# FPGA.net
KiCad netlist of a schematic drawn in Altium Designer
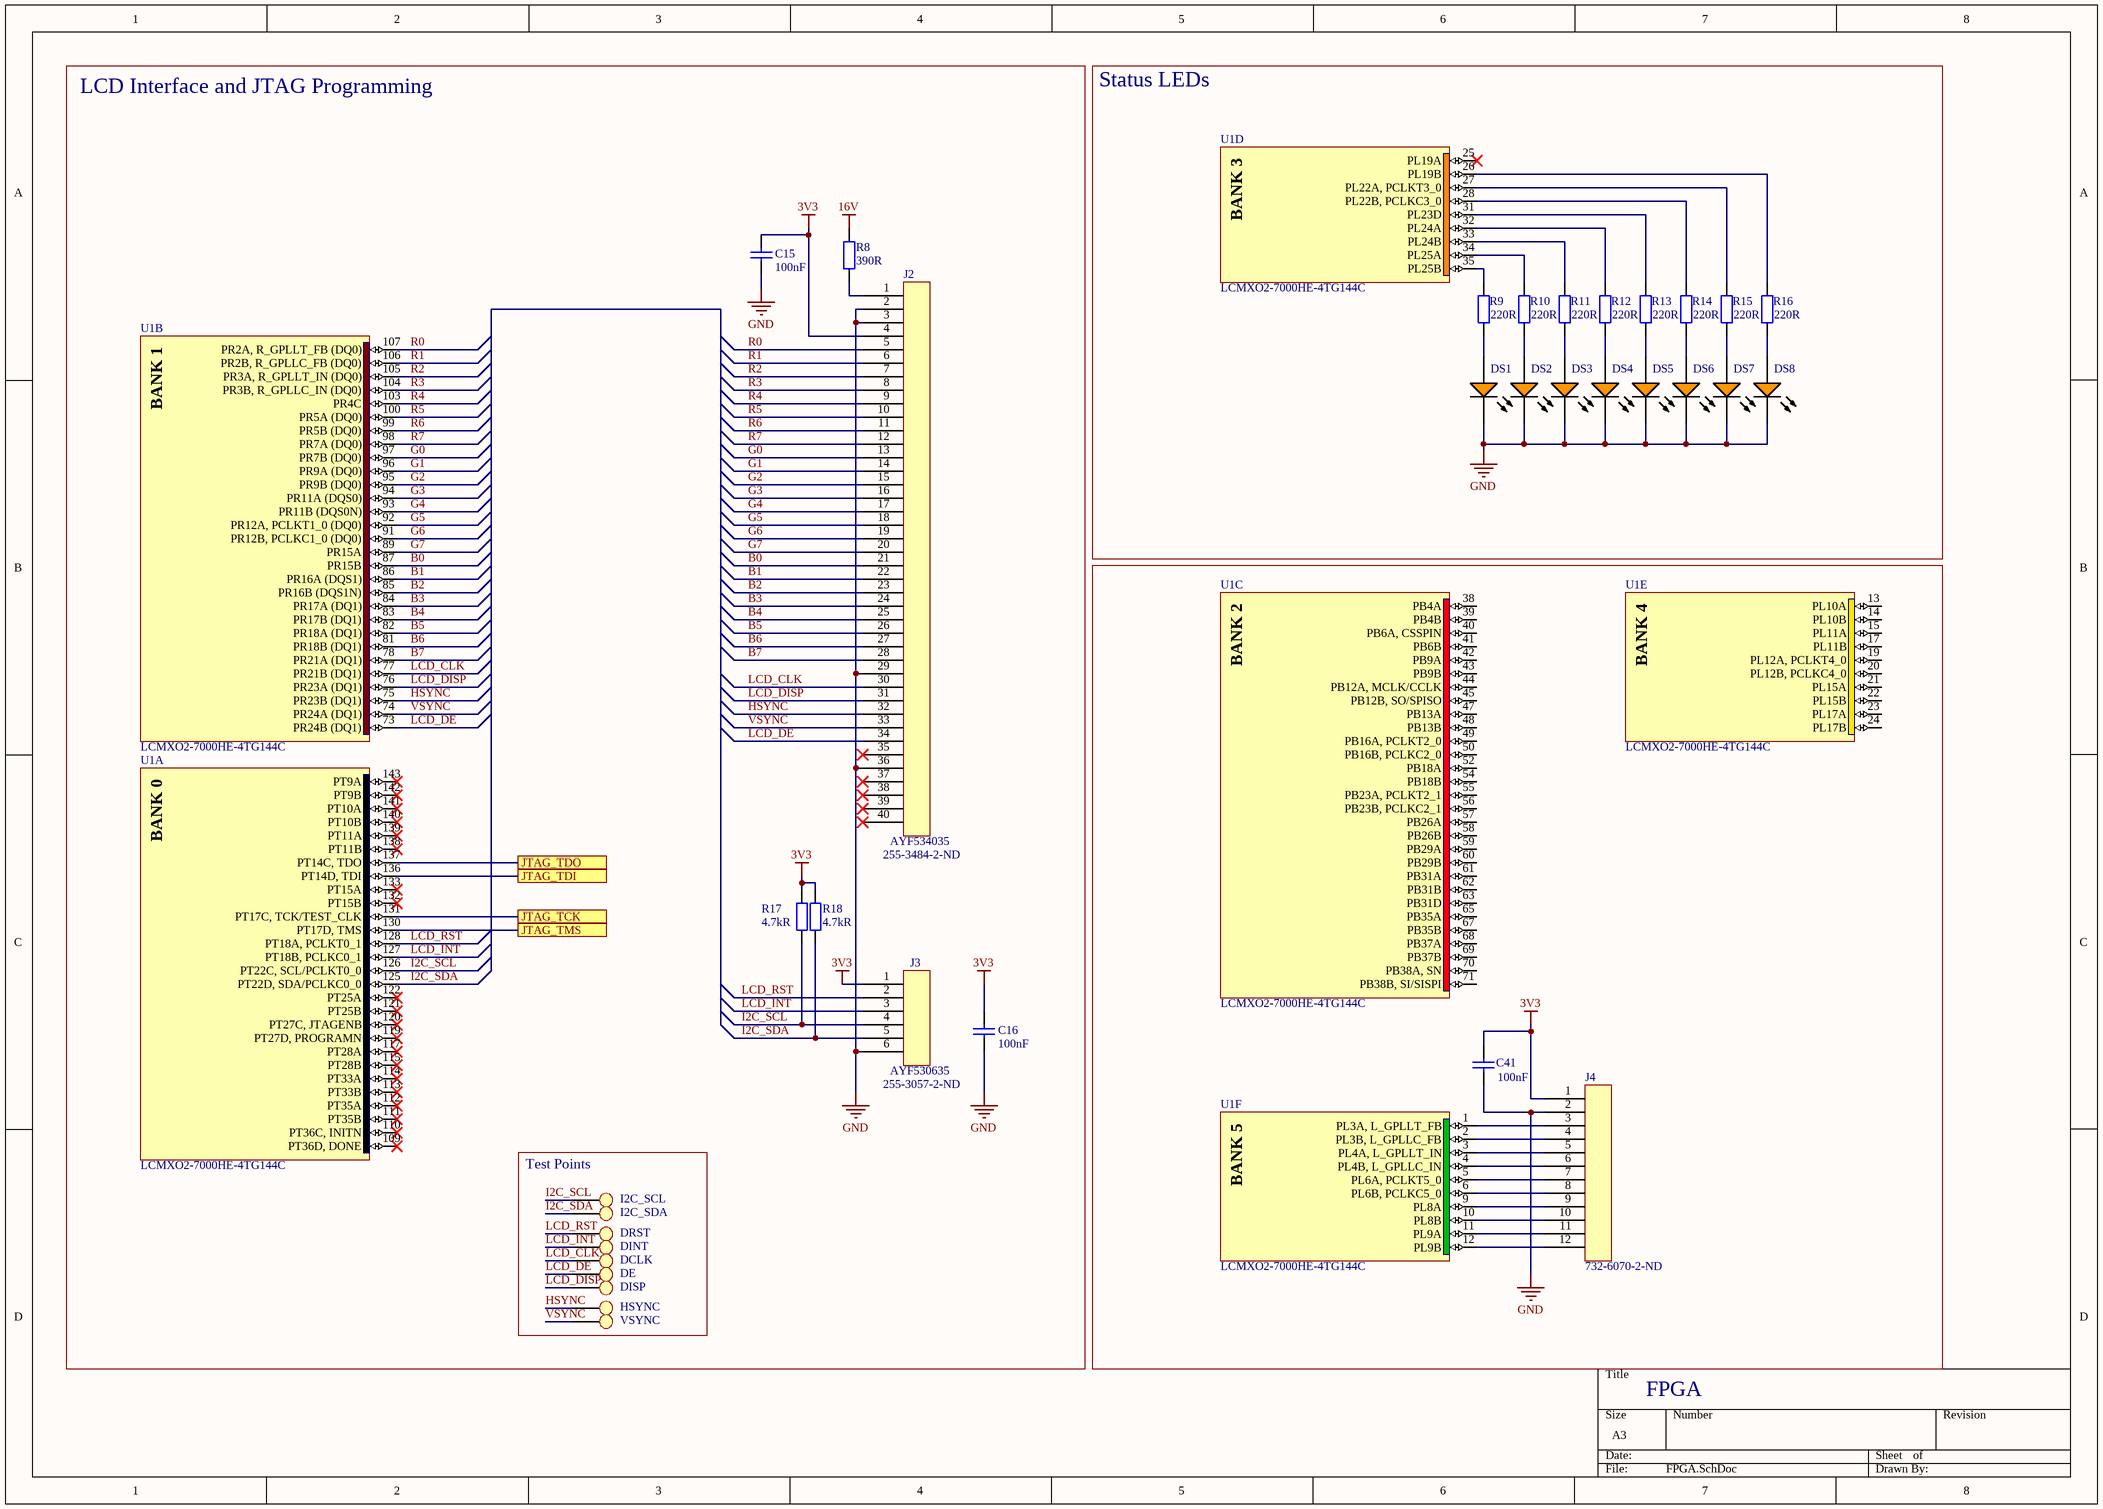
[diagram p0: FPGA.SchDoc]

(export (version "E")
  (design (tool "Eeschema 10.0.6"))
  (components
    (comp (ref "C15")
      (value "C0402C104K4RACTU")
      (footprint "CAP_0402_imperial")
      (description "CAP CER 0.1UF 16V X7R 0402")
      (fields
        (field (name "MANUFACTURER") "KEMET")
        (field (name "MANUFACTURER PART NUMBER") "C0402C104K4RAC-TU")
        (field (name "CAPACITANCE") "100nF")
      )
      (libsource (lib "LCD-Controller") (part "C0402C104K4RAC-TU"))
    )
    (comp (ref "C16")
      (value "C0402C104K4RACTU")
      (footprint "CAP_0402_imperial")
      (description "CAP CER 0.1UF 16V X7R 0402")
      (fields
        (field (name "MANUFACTURER") "KEMET")
        (field (name "MANUFACTURER PART NUMBER") "C0402C104K4RAC-TU")
        (field (name "CAPACITANCE") "100nF")
      )
      (libsource (lib "LCD-Controller") (part "C0402C104K4RAC-TU"))
    )
    (comp (ref "C41")
      (value "C0402C104K4RAC-TU")
      (footprint "CAP_0402_imperial")
      (description "CAP CER 0.1UF 16V X7R 0402")
      (fields
        (field (name "MANUFACTURER") "KEMET")
        (field (name "TOLERANCE") "10%")
        (field (name "CAPACITANCE") "100nF")
      )
      (libsource (lib "LCD-Controller") (part "C0402C104K4RAC-TU"))
    )
    (comp (ref "DCLK") (value "TP") (footprint "TP_0.75DIA") (libsource (lib "LCD-Controller") (part "TP")))
    (comp (ref "DE") (value "TP") (footprint "TP_0.75DIA") (libsource (lib "LCD-Controller") (part "TP")))
    (comp (ref "DINT") (value "TP") (footprint "TP_0.75DIA") (libsource (lib "LCD-Controller") (part "TP")))
    (comp (ref "DISP") (value "TP") (footprint "TP_0.75DIA") (libsource (lib "LCD-Controller") (part "TP")))
    (comp (ref "DRST") (value "TP") (footprint "TP_0.75DIA") (libsource (lib "LCD-Controller") (part "TP")))
    (comp (ref "DS1")
      (value "APG1608SEKC/T")
      (footprint "KING-LED0603-25-ORANGE_V")
      (description "LED, SMT, 0603(1608), 0.25mm Tthickness, Super Bright Orange")
      (libsource (lib "Altium Content Vault") (part "KING-LED_ORANGE_A1K2-2"))
    )
    (comp (ref "DS2")
      (value "APG1608SEKC/T")
      (footprint "KING-LED0603-25-ORANGE_V")
      (description "LED, SMT, 0603(1608), 0.25mm Tthickness, Super Bright Orange")
      (libsource (lib "Altium Content Vault") (part "KING-LED_ORANGE_A1K2-2"))
    )
    (comp (ref "DS3")
      (value "APG1608SEKC/T")
      (footprint "KING-LED0603-25-ORANGE_V")
      (description "LED, SMT, 0603(1608), 0.25mm Tthickness, Super Bright Orange")
      (libsource (lib "Altium Content Vault") (part "KING-LED_ORANGE_A1K2-2"))
    )
    (comp (ref "DS4")
      (value "APG1608SEKC/T")
      (footprint "KING-LED0603-25-ORANGE_V")
      (description "LED, SMT, 0603(1608), 0.25mm Tthickness, Super Bright Orange")
      (libsource (lib "Altium Content Vault") (part "KING-LED_ORANGE_A1K2-2"))
    )
    (comp (ref "DS5")
      (value "APG1608SEKC/T")
      (footprint "KING-LED0603-25-ORANGE_V")
      (description "LED, SMT, 0603(1608), 0.25mm Tthickness, Super Bright Orange")
      (libsource (lib "Altium Content Vault") (part "KING-LED_ORANGE_A1K2-2"))
    )
    (comp (ref "DS6")
      (value "APG1608SEKC/T")
      (footprint "KING-LED0603-25-ORANGE_V")
      (description "LED, SMT, 0603(1608), 0.25mm Tthickness, Super Bright Orange")
      (libsource (lib "Altium Content Vault") (part "KING-LED_ORANGE_A1K2-2"))
    )
    (comp (ref "DS7")
      (value "APG1608SEKC/T")
      (footprint "KING-LED0603-25-ORANGE_V")
      (description "LED, SMT, 0603(1608), 0.25mm Tthickness, Super Bright Orange")
      (libsource (lib "Altium Content Vault") (part "KING-LED_ORANGE_A1K2-2"))
    )
    (comp (ref "DS8")
      (value "APG1608SEKC/T")
      (footprint "KING-LED0603-25-ORANGE_V")
      (description "LED, SMT, 0603(1608), 0.25mm Tthickness, Super Bright Orange")
      (libsource (lib "Altium Content Vault") (part "KING-LED_ORANGE_A1K2-2"))
    )
    (comp (ref "HSYNC") (value "TP") (footprint "TP_0.75DIA") (libsource (lib "LCD-Controller") (part "TP")))
    (comp (ref "I2C_SCL")
      (value "TP")
      (footprint "TP_0.75DIA")
      (libsource (lib "LCD-Controller") (part "TP"))
    )
    (comp (ref "I2C_SDA")
      (value "TP")
      (footprint "TP_0.75DIA")
      (libsource (lib "LCD-Controller") (part "TP"))
    )
    (comp (ref "J2")
      (value "AYF534035")
      (footprint "AYF534035")
      (description "CONN FFC FPC 40POS 0.50MM R/A")
      (fields
        (field (name "MANUFACTURER") "Panasonic")
        (field (name "SUPPLIER PART NUMBER 1") "255-3484-2-ND")
      )
      (libsource (lib "Connectors") (part "AYF534035"))
    )
    (comp (ref "J3")
      (value "AYF530635")
      (footprint "AYF530635")
      (description "CONN FFC FPC 6POS 0.50MM R/A")
      (fields
        (field (name "MANUFACTURER") "Panasonic")
        (field (name "SUPPLIER PART NUMBER 1") "255-3057-2-ND")
      )
      (libsource (lib "Connectors") (part "AYF530635"))
    )
    (comp (ref "J4")
      (value "610112249121")
      (footprint "610112249121")
      (description "Pin header 12P, 610112249121, Würth Elektronik")
      (fields
        (field (name "MANUFACTURER") "Wurth Electronics")
        (field (name "SUPPLIER PART NUMBER 1") "732-6070-2-ND")
      )
      (libsource (lib "LCD-Controller") (part "610112249121"))
    )
    (comp (ref "R8")
      (value "390R 1% 2512(6432)")
      (footprint "RES_0603_imperial")
      (fields
        (field (name "TOLERANCE") "0.1%")
        (field (name "MANUFACTURER") "Panasonic")
        (field (name "MANUFACTURER PART NUMBER") "ERA3AEB391V")
        (field (name "RESISTANCE") "390R")
      )
      (libsource (lib "LCD-Controller") (part "ERA3AEB391V"))
    )
    (comp (ref "R9")
      (value "220R 1% 0603(1608)")
      (footprint "RES_0603_imperial")
      (description "Res Thin Film 0603 220 Ohm 0.1% 1/10W ±25ppm/C Molded SMD Punched Carrier T/R")
      (fields
        (field (name "TOLERANCE") "0.1%")
        (field (name "MANUFACTURER") "Panasonic")
        (field (name "RESISTANCE") "220R")
      )
      (libsource (lib "LCD-Controller") (part "ERA-3AEB221V"))
    )
    (comp (ref "R10")
      (value "220R 1% 0603(1608)")
      (footprint "RES_0603_imperial")
      (description "Res Thin Film 0603 220 Ohm 0.1% 1/10W ±25ppm/C Molded SMD Punched Carrier T/R")
      (fields
        (field (name "TOLERANCE") "0.1%")
        (field (name "MANUFACTURER") "Panasonic")
        (field (name "RESISTANCE") "220R")
      )
      (libsource (lib "LCD-Controller") (part "ERA-3AEB221V"))
    )
    (comp (ref "R11")
      (value "220R 1% 0603(1608)")
      (footprint "RES_0603_imperial")
      (description "Res Thin Film 0603 220 Ohm 0.1% 1/10W ±25ppm/C Molded SMD Punched Carrier T/R")
      (fields
        (field (name "TOLERANCE") "0.1%")
        (field (name "MANUFACTURER") "Panasonic")
        (field (name "RESISTANCE") "220R")
      )
      (libsource (lib "LCD-Controller") (part "ERA-3AEB221V"))
    )
    (comp (ref "R12")
      (value "220R 1% 0603(1608)")
      (footprint "RES_0603_imperial")
      (description "Res Thin Film 0603 220 Ohm 0.1% 1/10W ±25ppm/C Molded SMD Punched Carrier T/R")
      (fields
        (field (name "TOLERANCE") "0.1%")
        (field (name "MANUFACTURER") "Panasonic")
        (field (name "RESISTANCE") "220R")
      )
      (libsource (lib "LCD-Controller") (part "ERA-3AEB221V"))
    )
    (comp (ref "R13")
      (value "220R 1% 0603(1608)")
      (footprint "RES_0603_imperial")
      (description "Res Thin Film 0603 220 Ohm 0.1% 1/10W ±25ppm/C Molded SMD Punched Carrier T/R")
      (fields
        (field (name "TOLERANCE") "0.1%")
        (field (name "MANUFACTURER") "Panasonic")
        (field (name "RESISTANCE") "220R")
      )
      (libsource (lib "LCD-Controller") (part "ERA-3AEB221V"))
    )
    (comp (ref "R14")
      (value "220R 1% 0603(1608)")
      (footprint "RES_0603_imperial")
      (description "Res Thin Film 0603 220 Ohm 0.1% 1/10W ±25ppm/C Molded SMD Punched Carrier T/R")
      (fields
        (field (name "TOLERANCE") "0.1%")
        (field (name "MANUFACTURER") "Panasonic")
        (field (name "RESISTANCE") "220R")
      )
      (libsource (lib "LCD-Controller") (part "ERA-3AEB221V"))
    )
    (comp (ref "R15")
      (value "220R 1% 0603(1608)")
      (footprint "RES_0603_imperial")
      (description "Res Thin Film 0603 220 Ohm 0.1% 1/10W ±25ppm/C Molded SMD Punched Carrier T/R")
      (fields
        (field (name "TOLERANCE") "0.1%")
        (field (name "MANUFACTURER") "Panasonic")
        (field (name "RESISTANCE") "220R")
      )
      (libsource (lib "LCD-Controller") (part "ERA-3AEB221V"))
    )
    (comp (ref "R16")
      (value "220R 1% 0603(1608)")
      (footprint "RES_0603_imperial")
      (description "Res Thin Film 0603 220 Ohm 0.1% 1/10W ±25ppm/C Molded SMD Punched Carrier T/R")
      (fields
        (field (name "TOLERANCE") "0.1%")
        (field (name "MANUFACTURER") "Panasonic")
        (field (name "RESISTANCE") "220R")
      )
      (libsource (lib "LCD-Controller") (part "ERA-3AEB221V"))
    )
    (comp (ref "R17")
      (value "4K7 1% 0603(1608)")
      (footprint "RES_0603_imperial")
      (description "Res Thin Film 0603 4.7K Ohm 0.1% 0.1W(1/10W) ±25ppm/C Molded SMD Automotive Punched T/R")
      (fields
        (field (name "TOLERANCE") "0.1%")
        (field (name "MANUFACTURER") "Panasonic")
        (field (name "RESISTANCE") "4.7kR")
      )
      (libsource (lib "LCD-Controller") (part "ERA-3AEB472V"))
    )
    (comp (ref "R18")
      (value "4K7 1% 0603(1608)")
      (footprint "RES_0603_imperial")
      (description "Res Thin Film 0603 4.7K Ohm 0.1% 0.1W(1/10W) ±25ppm/C Molded SMD Automotive Punched T/R")
      (fields
        (field (name "TOLERANCE") "0.1%")
        (field (name "MANUFACTURER") "Panasonic")
        (field (name "RESISTANCE") "4.7kR")
      )
      (libsource (lib "LCD-Controller") (part "ERA-3AEB472V"))
    )
    (comp (ref "U1")
      (value "LCMXO2-7000HE-4TG144C")
      (footprint "TQFP144_L")
      (libsource (lib "Altium Content Vault") (part "PLD-LTMXO2-7000-TQ144"))
    )
    (comp (ref "VSYNC") (value "TP") (footprint "TP_0.75DIA") (libsource (lib "LCD-Controller") (part "TP")))
  )
  (nets
    (net (code "1") (name "/B0") (class "Default")
      (node (ref "J2") (pin "21") (pintype "passive"))
      (node (ref "U1") (pin "87") (pinfunction "PR15B_87") (pintype "bidirectional"))
    )
    (net (code "2") (name "/B1") (class "Default")
      (node (ref "J2") (pin "22") (pintype "passive"))
      (node (ref "U1") (pin "86") (pinfunction "PR16A_(DQS1)_86") (pintype "bidirectional"))
    )
    (net (code "3") (name "/B2") (class "Default")
      (node (ref "J2") (pin "23") (pintype "passive"))
      (node (ref "U1") (pin "85") (pinfunction "PR16B_(DQS1N)_85") (pintype "bidirectional"))
    )
    (net (code "4") (name "/B3") (class "Default")
      (node (ref "J2") (pin "24") (pintype "passive"))
      (node (ref "U1") (pin "84") (pinfunction "PR17A_(DQ1)_84") (pintype "bidirectional"))
    )
    (net (code "5") (name "/B4") (class "Default")
      (node (ref "J2") (pin "25") (pintype "passive"))
      (node (ref "U1") (pin "83") (pinfunction "PR17B_(DQ1)_83") (pintype "bidirectional"))
    )
    (net (code "6") (name "/B5") (class "Default")
      (node (ref "J2") (pin "26") (pintype "passive"))
      (node (ref "U1") (pin "82") (pinfunction "PR18A_(DQ1)_82") (pintype "bidirectional"))
    )
    (net (code "7") (name "/B6") (class "Default")
      (node (ref "J2") (pin "27") (pintype "passive"))
      (node (ref "U1") (pin "81") (pinfunction "PR18B_(DQ1)_81") (pintype "bidirectional"))
    )
    (net (code "8") (name "/B7") (class "Default")
      (node (ref "J2") (pin "28") (pintype "passive"))
      (node (ref "U1") (pin "78") (pinfunction "PR21A_(DQ1)_78") (pintype "bidirectional"))
    )
    (net (code "9") (name "/G0") (class "Default")
      (node (ref "J2") (pin "13") (pintype "passive"))
      (node (ref "U1") (pin "97") (pinfunction "PR7B_(DQ0)_97") (pintype "bidirectional"))
    )
    (net (code "10") (name "/G1") (class "Default")
      (node (ref "J2") (pin "14") (pintype "passive"))
      (node (ref "U1") (pin "96") (pinfunction "PR9A_(DQ0)_96") (pintype "bidirectional"))
    )
    (net (code "11") (name "/G2") (class "Default")
      (node (ref "J2") (pin "15") (pintype "passive"))
      (node (ref "U1") (pin "95") (pinfunction "PR9B_(DQ0)_95") (pintype "bidirectional"))
    )
    (net (code "12") (name "/G3") (class "Default")
      (node (ref "J2") (pin "16") (pintype "passive"))
      (node (ref "U1") (pin "94") (pinfunction "PR11A_(DQS0)_94") (pintype "bidirectional"))
    )
    (net (code "13") (name "/G4") (class "Default")
      (node (ref "J2") (pin "17") (pintype "passive"))
      (node (ref "U1") (pin "93") (pinfunction "PR11B_(DQS0N)_93") (pintype "bidirectional"))
    )
    (net (code "14") (name "/G5") (class "Default")
      (node (ref "J2") (pin "18") (pintype "passive"))
      (node (ref "U1") (pin "92") (pinfunction "PR12A,_PCLKT1_0_(DQ0)_92") (pintype "bidirectional"))
    )
    (net (code "15") (name "/G6") (class "Default")
      (node (ref "J2") (pin "19") (pintype "passive"))
      (node (ref "U1") (pin "91") (pinfunction "PR12B,_PCLKC1_0_(DQ0)_91") (pintype "bidirectional"))
    )
    (net (code "16") (name "/G7") (class "Default")
      (node (ref "J2") (pin "20") (pintype "passive"))
      (node (ref "U1") (pin "89") (pinfunction "PR15A_89") (pintype "bidirectional"))
    )
    (net (code "17") (name "/HSYNC") (class "Default")
      (node (ref "HSYNC") (pin "1") (pinfunction "1_1") (pintype "passive"))
      (node (ref "J2") (pin "32") (pintype "passive"))
      (node (ref "U1") (pin "75") (pinfunction "PR23B_(DQ1)_75") (pintype "bidirectional"))
    )
    (net (code "18") (name "/I2C_SCL") (class "Default")
      (node (ref "I2C_SCL") (pin "1") (pinfunction "1_1") (pintype "passive"))
      (node (ref "J3") (pin "4") (pintype "passive"))
      (node (ref "R17") (pin "1") (pinfunction "1_1") (pintype "passive"))
      (node (ref "U1") (pin "126") (pinfunction "PT22C,_SCL/PCLKT0_0_126") (pintype "bidirectional"))
    )
    (net (code "19") (name "/I2C_SDA") (class "Default")
      (node (ref "I2C_SDA") (pin "1") (pinfunction "1_1") (pintype "passive"))
      (node (ref "J3") (pin "5") (pintype "passive"))
      (node (ref "R18") (pin "1") (pinfunction "1_1") (pintype "passive"))
      (node (ref "U1") (pin "125") (pinfunction "PT22D,_SDA/PCLKC0_0_125") (pintype "bidirectional"))
    )
    (net (code "20") (name "/JTAG_TCK") (class "Default")
      (node (ref "U1") (pin "131") (pinfunction "PT17C,_TCK/TEST_CLK_131") (pintype "bidirectional"))
    )
    (net (code "21") (name "/JTAG_TDI") (class "Default")
      (node (ref "U1") (pin "136") (pinfunction "PT14D,_TDI_136") (pintype "bidirectional"))
    )
    (net (code "22") (name "/JTAG_TDO") (class "Default")
      (node (ref "U1") (pin "137") (pinfunction "PT14C,_TDO_137") (pintype "bidirectional"))
    )
    (net (code "23") (name "/JTAG_TMS") (class "Default")
      (node (ref "U1") (pin "130") (pinfunction "PT17D,_TMS_130") (pintype "bidirectional"))
    )
    (net (code "24") (name "/LCD_CLK") (class "Default")
      (node (ref "DCLK") (pin "1") (pinfunction "1_1") (pintype "passive"))
      (node (ref "J2") (pin "30") (pintype "passive"))
      (node (ref "U1") (pin "77") (pinfunction "PR21B_(DQ1)_77") (pintype "bidirectional"))
    )
    (net (code "25") (name "/LCD_DE") (class "Default")
      (node (ref "DE") (pin "1") (pinfunction "1_1") (pintype "passive"))
      (node (ref "J2") (pin "34") (pintype "passive"))
      (node (ref "U1") (pin "73") (pinfunction "PR24B_(DQ1)_73") (pintype "bidirectional"))
    )
    (net (code "26") (name "/LCD_DISP") (class "Default")
      (node (ref "DISP") (pin "1") (pinfunction "1_1") (pintype "passive"))
      (node (ref "J2") (pin "31") (pintype "passive"))
      (node (ref "U1") (pin "76") (pinfunction "PR23A_(DQ1)_76") (pintype "bidirectional"))
    )
    (net (code "27") (name "/LCD_INT") (class "Default")
      (node (ref "DINT") (pin "1") (pinfunction "1_1") (pintype "passive"))
      (node (ref "J3") (pin "3") (pintype "passive"))
      (node (ref "U1") (pin "127") (pinfunction "PT18B,_PCLKC0_1_127") (pintype "bidirectional"))
    )
    (net (code "28") (name "/LCD_RST") (class "Default")
      (node (ref "DRST") (pin "1") (pinfunction "1_1") (pintype "passive"))
      (node (ref "J3") (pin "2") (pintype "passive"))
      (node (ref "U1") (pin "128") (pinfunction "PT18A,_PCLKT0_1_128") (pintype "bidirectional"))
    )
    (net (code "29") (name "/R0") (class "Default")
      (node (ref "J2") (pin "5") (pintype "passive"))
      (node (ref "U1") (pin "107") (pinfunction "PR2A,_R_GPLLT_FB_(DQ0)_107") (pintype "bidirectional"))
    )
    (net (code "30") (name "/R1") (class "Default")
      (node (ref "J2") (pin "6") (pintype "passive"))
      (node (ref "U1") (pin "106") (pinfunction "PR2B,_R_GPLLC_FB_(DQ0)_106") (pintype "bidirectional"))
    )
    (net (code "31") (name "/R2") (class "Default")
      (node (ref "J2") (pin "7") (pintype "passive"))
      (node (ref "U1") (pin "105") (pinfunction "PR3A,_R_GPLLT_IN_(DQ0)_105") (pintype "bidirectional"))
    )
    (net (code "32") (name "/R3") (class "Default")
      (node (ref "J2") (pin "8") (pintype "passive"))
      (node (ref "U1") (pin "104") (pinfunction "PR3B,_R_GPLLC_IN_(DQ0)_104") (pintype "bidirectional"))
    )
    (net (code "33") (name "/R4") (class "Default")
      (node (ref "J2") (pin "9") (pintype "passive"))
      (node (ref "U1") (pin "103") (pinfunction "PR4C_103") (pintype "bidirectional"))
    )
    (net (code "34") (name "/R5") (class "Default")
      (node (ref "J2") (pin "10") (pintype "passive"))
      (node (ref "U1") (pin "100") (pinfunction "PR5A_(DQ0)_100") (pintype "bidirectional"))
    )
    (net (code "35") (name "/R6") (class "Default")
      (node (ref "J2") (pin "11") (pintype "passive"))
      (node (ref "U1") (pin "99") (pinfunction "PR5B_(DQ0)_99") (pintype "bidirectional"))
    )
    (net (code "36") (name "/R7") (class "Default")
      (node (ref "J2") (pin "12") (pintype "passive"))
      (node (ref "U1") (pin "98") (pinfunction "PR7A_(DQ0)_98") (pintype "bidirectional"))
    )
    (net (code "37") (name "/VSYNC") (class "Default")
      (node (ref "J2") (pin "33") (pintype "passive"))
      (node (ref "U1") (pin "74") (pinfunction "PR24A_(DQ1)_74") (pintype "bidirectional"))
      (node (ref "VSYNC") (pin "1") (pinfunction "1_1") (pintype "passive"))
    )
    (net (code "38") (name "3V3") (class "Default")
      (node (ref "C15") (pin "1") (pinfunction "1_1") (pintype "passive"))
      (node (ref "C16") (pin "1") (pinfunction "1_1") (pintype "passive"))
      (node (ref "C41") (pin "2") (pinfunction "2_2") (pintype "passive"))
      (node (ref "J2") (pin "4") (pintype "passive"))
      (node (ref "J3") (pin "1") (pintype "passive"))
      (node (ref "J4") (pin "1") (pintype "passive"))
      (node (ref "R17") (pin "2") (pinfunction "2_2") (pintype "passive"))
      (node (ref "R18") (pin "2") (pinfunction "2_2") (pintype "passive"))
    )
    (net (code "39") (name "16V") (class "Default")
      (node (ref "R8") (pin "2") (pinfunction "2_2") (pintype "passive"))
    )
    (net (code "40") (name "GND") (class "Default")
      (node (ref "C15") (pin "2") (pinfunction "2_2") (pintype "passive"))
      (node (ref "C16") (pin "2") (pinfunction "2_2") (pintype "passive"))
      (node (ref "C41") (pin "1") (pinfunction "1_1") (pintype "passive"))
      (node (ref "DS1") (pin "2") (pinfunction "K_2") (pintype "passive"))
      (node (ref "DS2") (pin "2") (pinfunction "K_2") (pintype "passive"))
      (node (ref "DS3") (pin "2") (pinfunction "K_2") (pintype "passive"))
      (node (ref "DS4") (pin "2") (pinfunction "K_2") (pintype "passive"))
      (node (ref "DS5") (pin "2") (pinfunction "K_2") (pintype "passive"))
      (node (ref "DS6") (pin "2") (pinfunction "K_2") (pintype "passive"))
      (node (ref "DS7") (pin "2") (pinfunction "K_2") (pintype "passive"))
      (node (ref "DS8") (pin "2") (pinfunction "K_2") (pintype "passive"))
      (node (ref "J2") (pin "2") (pintype "passive"))
      (node (ref "J2") (pin "29") (pintype "passive"))
      (node (ref "J2") (pin "3") (pintype "passive"))
      (node (ref "J2") (pin "36") (pintype "passive"))
      (node (ref "J3") (pin "6") (pintype "passive"))
      (node (ref "J4") (pin "2") (pintype "passive"))
    )
    (net (code "41") (name "Net-(DS1-A)") (class "Default")
      (node (ref "DS1") (pin "1") (pinfunction "A_1") (pintype "passive"))
      (node (ref "R9") (pin "1") (pinfunction "1_1") (pintype "passive"))
    )
    (net (code "42") (name "Net-(DS2-A)") (class "Default")
      (node (ref "DS2") (pin "1") (pinfunction "A_1") (pintype "passive"))
      (node (ref "R10") (pin "1") (pinfunction "1_1") (pintype "passive"))
    )
    (net (code "43") (name "Net-(DS3-A)") (class "Default")
      (node (ref "DS3") (pin "1") (pinfunction "A_1") (pintype "passive"))
      (node (ref "R11") (pin "1") (pinfunction "1_1") (pintype "passive"))
    )
    (net (code "44") (name "Net-(DS4-A)") (class "Default")
      (node (ref "DS4") (pin "1") (pinfunction "A_1") (pintype "passive"))
      (node (ref "R12") (pin "1") (pinfunction "1_1") (pintype "passive"))
    )
    (net (code "45") (name "Net-(DS5-A)") (class "Default")
      (node (ref "DS5") (pin "1") (pinfunction "A_1") (pintype "passive"))
      (node (ref "R13") (pin "1") (pinfunction "1_1") (pintype "passive"))
    )
    (net (code "46") (name "Net-(DS6-A)") (class "Default")
      (node (ref "DS6") (pin "1") (pinfunction "A_1") (pintype "passive"))
      (node (ref "R14") (pin "1") (pinfunction "1_1") (pintype "passive"))
    )
    (net (code "47") (name "Net-(DS7-A)") (class "Default")
      (node (ref "DS7") (pin "1") (pinfunction "A_1") (pintype "passive"))
      (node (ref "R15") (pin "1") (pinfunction "1_1") (pintype "passive"))
    )
    (net (code "48") (name "Net-(DS8-A)") (class "Default")
      (node (ref "DS8") (pin "1") (pinfunction "A_1") (pintype "passive"))
      (node (ref "R16") (pin "1") (pinfunction "1_1") (pintype "passive"))
    )
    (net (code "49") (name "Net-(J2-Pad1)") (class "Default")
      (node (ref "J2") (pin "1") (pintype "passive"))
      (node (ref "R8") (pin "1") (pinfunction "1_1") (pintype "passive"))
    )
    (net (code "50") (name "Net-(U1D-PL19B)") (class "Default")
      (node (ref "R16") (pin "2") (pinfunction "2_2") (pintype "passive"))
      (node (ref "U1") (pin "26") (pinfunction "PL19B_26") (pintype "bidirectional"))
    )
    (net (code "51") (name "Net-(U1D-PL22A,_PCLKT3_0)") (class "Default")
      (node (ref "R15") (pin "2") (pinfunction "2_2") (pintype "passive"))
      (node (ref "U1") (pin "27") (pinfunction "PL22A,_PCLKT3_0_27") (pintype "bidirectional"))
    )
    (net (code "52") (name "Net-(U1D-PL22B,_PCLKC3_0)") (class "Default")
      (node (ref "R14") (pin "2") (pinfunction "2_2") (pintype "passive"))
      (node (ref "U1") (pin "28") (pinfunction "PL22B,_PCLKC3_0_28") (pintype "bidirectional"))
    )
    (net (code "53") (name "Net-(U1D-PL23D)") (class "Default")
      (node (ref "R13") (pin "2") (pinfunction "2_2") (pintype "passive"))
      (node (ref "U1") (pin "31") (pinfunction "PL23D_31") (pintype "bidirectional"))
    )
    (net (code "54") (name "Net-(U1D-PL24A)") (class "Default")
      (node (ref "R12") (pin "2") (pinfunction "2_2") (pintype "passive"))
      (node (ref "U1") (pin "32") (pinfunction "PL24A_32") (pintype "bidirectional"))
    )
    (net (code "55") (name "Net-(U1D-PL24B)") (class "Default")
      (node (ref "R11") (pin "2") (pinfunction "2_2") (pintype "passive"))
      (node (ref "U1") (pin "33") (pinfunction "PL24B_33") (pintype "bidirectional"))
    )
    (net (code "56") (name "Net-(U1D-PL25A)") (class "Default")
      (node (ref "R10") (pin "2") (pinfunction "2_2") (pintype "passive"))
      (node (ref "U1") (pin "34") (pinfunction "PL25A_34") (pintype "bidirectional"))
    )
    (net (code "57") (name "Net-(U1D-PL25B)") (class "Default")
      (node (ref "R9") (pin "2") (pinfunction "2_2") (pintype "passive"))
      (node (ref "U1") (pin "35") (pinfunction "PL25B_35") (pintype "bidirectional"))
    )
    (net (code "58") (name "Net-(U1F-PL3A,_L_GPLLT_FB)") (class "Default")
      (node (ref "J4") (pin "3") (pintype "passive"))
      (node (ref "U1") (pin "1") (pinfunction "PL3A,_L_GPLLT_FB_1") (pintype "bidirectional"))
    )
    (net (code "59") (name "Net-(U1F-PL3B,_L_GPLLC_FB)") (class "Default")
      (node (ref "J4") (pin "4") (pintype "passive"))
      (node (ref "U1") (pin "2") (pinfunction "PL3B,_L_GPLLC_FB_2") (pintype "bidirectional"))
    )
    (net (code "60") (name "Net-(U1F-PL4A,_L_GPLLT_IN)") (class "Default")
      (node (ref "J4") (pin "5") (pintype "passive"))
      (node (ref "U1") (pin "3") (pinfunction "PL4A,_L_GPLLT_IN_3") (pintype "bidirectional"))
    )
    (net (code "61") (name "Net-(U1F-PL4B,_L_GPLLC_IN)") (class "Default")
      (node (ref "J4") (pin "6") (pintype "passive"))
      (node (ref "U1") (pin "4") (pinfunction "PL4B,_L_GPLLC_IN_4") (pintype "bidirectional"))
    )
    (net (code "62") (name "Net-(U1F-PL6A,_PCLKT5_0)") (class "Default")
      (node (ref "J4") (pin "7") (pintype "passive"))
      (node (ref "U1") (pin "5") (pinfunction "PL6A,_PCLKT5_0_5") (pintype "bidirectional"))
    )
    (net (code "63") (name "Net-(U1F-PL6B,_PCLKC5_0)") (class "Default")
      (node (ref "J4") (pin "8") (pintype "passive"))
      (node (ref "U1") (pin "6") (pinfunction "PL6B,_PCLKC5_0_6") (pintype "bidirectional"))
    )
    (net (code "64") (name "Net-(U1F-PL8A)") (class "Default")
      (node (ref "J4") (pin "9") (pintype "passive"))
      (node (ref "U1") (pin "9") (pinfunction "PL8A_9") (pintype "bidirectional"))
    )
    (net (code "65") (name "Net-(U1F-PL8B)") (class "Default")
      (node (ref "J4") (pin "10") (pintype "passive"))
      (node (ref "U1") (pin "10") (pinfunction "PL8B_10") (pintype "bidirectional"))
    )
    (net (code "66") (name "Net-(U1F-PL9A)") (class "Default")
      (node (ref "J4") (pin "11") (pintype "passive"))
      (node (ref "U1") (pin "11") (pinfunction "PL9A_11") (pintype "bidirectional"))
    )
    (net (code "67") (name "Net-(U1F-PL9B)") (class "Default")
      (node (ref "J4") (pin "12") (pintype "passive"))
      (node (ref "U1") (pin "12") (pinfunction "PL9B_12") (pintype "bidirectional"))
    )
    (net (code "68") (name "unconnected-(J2-Pad35)") (class "Default")
      (node (ref "J2") (pin "35") (pintype "passive+no_connect"))
    )
    (net (code "69") (name "unconnected-(J2-Pad37)") (class "Default")
      (node (ref "J2") (pin "37") (pintype "passive+no_connect"))
    )
    (net (code "70") (name "unconnected-(J2-Pad38)") (class "Default")
      (node (ref "J2") (pin "38") (pintype "passive+no_connect"))
    )
    (net (code "71") (name "unconnected-(J2-Pad39)") (class "Default")
      (node (ref "J2") (pin "39") (pintype "passive+no_connect"))
    )
    (net (code "72") (name "unconnected-(J2-Pad40)") (class "Default")
      (node (ref "J2") (pin "40") (pintype "passive+no_connect"))
    )
    (net (code "73") (name "unconnected-(U1A-PT9A-Pad143)") (class "Default")
      (node (ref "U1") (pin "143") (pinfunction "PT9A_143") (pintype "bidirectional+no_connect"))
    )
    (net (code "74") (name "unconnected-(U1A-PT9B-Pad142)") (class "Default")
      (node (ref "U1") (pin "142") (pinfunction "PT9B_142") (pintype "bidirectional+no_connect"))
    )
    (net (code "75") (name "unconnected-(U1A-PT10A-Pad141)") (class "Default")
      (node (ref "U1") (pin "141") (pinfunction "PT10A_141") (pintype "bidirectional+no_connect"))
    )
    (net (code "76") (name "unconnected-(U1A-PT10B-Pad140)") (class "Default")
      (node (ref "U1") (pin "140") (pinfunction "PT10B_140") (pintype "bidirectional+no_connect"))
    )
    (net (code "77") (name "unconnected-(U1A-PT11A-Pad139)") (class "Default")
      (node (ref "U1") (pin "139") (pinfunction "PT11A_139") (pintype "bidirectional+no_connect"))
    )
    (net (code "78") (name "unconnected-(U1A-PT11B-Pad138)") (class "Default")
      (node (ref "U1") (pin "138") (pinfunction "PT11B_138") (pintype "bidirectional+no_connect"))
    )
    (net (code "79") (name "unconnected-(U1A-PT15A-Pad133)") (class "Default")
      (node (ref "U1") (pin "133") (pinfunction "PT15A_133") (pintype "bidirectional+no_connect"))
    )
    (net (code "80") (name "unconnected-(U1A-PT15B-Pad132)") (class "Default")
      (node (ref "U1") (pin "132") (pinfunction "PT15B_132") (pintype "bidirectional+no_connect"))
    )
    (net (code "81") (name "unconnected-(U1A-PT25A-Pad122)") (class "Default")
      (node (ref "U1") (pin "122") (pinfunction "PT25A_122") (pintype "bidirectional+no_connect"))
    )
    (net (code "82") (name "unconnected-(U1A-PT25B-Pad121)") (class "Default")
      (node (ref "U1") (pin "121") (pinfunction "PT25B_121") (pintype "bidirectional+no_connect"))
    )
    (net (code "83") (name "unconnected-(U1A-PT27C,_JTAGENB-Pad120)") (class "Default")
      (node (ref "U1") (pin "120") (pinfunction "PT27C,_JTAGENB_120") (pintype "bidirectional+no_connect"))
    )
    (net (code "84") (name "unconnected-(U1A-PT27D,_PROGRAMN-Pad119)") (class "Default")
      (node (ref "U1") (pin "119") (pinfunction "PT27D,_PROGRAMN_119") (pintype "bidirectional+no_connect"))
    )
    (net (code "85") (name "unconnected-(U1A-PT28A-Pad117)") (class "Default")
      (node (ref "U1") (pin "117") (pinfunction "PT28A_117") (pintype "bidirectional+no_connect"))
    )
    (net (code "86") (name "unconnected-(U1A-PT28B-Pad115)") (class "Default")
      (node (ref "U1") (pin "115") (pinfunction "PT28B_115") (pintype "bidirectional+no_connect"))
    )
    (net (code "87") (name "unconnected-(U1A-PT33A-Pad114)") (class "Default")
      (node (ref "U1") (pin "114") (pinfunction "PT33A_114") (pintype "bidirectional+no_connect"))
    )
    (net (code "88") (name "unconnected-(U1A-PT33B-Pad113)") (class "Default")
      (node (ref "U1") (pin "113") (pinfunction "PT33B_113") (pintype "bidirectional+no_connect"))
    )
    (net (code "89") (name "unconnected-(U1A-PT35A-Pad112)") (class "Default")
      (node (ref "U1") (pin "112") (pinfunction "PT35A_112") (pintype "bidirectional+no_connect"))
    )
    (net (code "90") (name "unconnected-(U1A-PT35B-Pad111)") (class "Default")
      (node (ref "U1") (pin "111") (pinfunction "PT35B_111") (pintype "bidirectional+no_connect"))
    )
    (net (code "91") (name "unconnected-(U1A-PT36C,_INITN-Pad110)") (class "Default")
      (node (ref "U1") (pin "110") (pinfunction "PT36C,_INITN_110") (pintype "bidirectional+no_connect"))
    )
    (net (code "92") (name "unconnected-(U1A-PT36D,_DONE-Pad109)") (class "Default")
      (node (ref "U1") (pin "109") (pinfunction "PT36D,_DONE_109") (pintype "bidirectional+no_connect"))
    )
    (net (code "93") (name "unconnected-(U1C-PB4A-Pad38)") (class "Default")
      (node (ref "U1") (pin "38") (pinfunction "PB4A_38") (pintype "bidirectional"))
    )
    (net (code "94") (name "unconnected-(U1C-PB4B-Pad39)") (class "Default")
      (node (ref "U1") (pin "39") (pinfunction "PB4B_39") (pintype "bidirectional"))
    )
    (net (code "95") (name "unconnected-(U1C-PB6A,_CSSPIN-Pad40)") (class "Default")
      (node (ref "U1") (pin "40") (pinfunction "PB6A,_CSSPIN_40") (pintype "bidirectional"))
    )
    (net (code "96") (name "unconnected-(U1C-PB6B-Pad41)") (class "Default")
      (node (ref "U1") (pin "41") (pinfunction "PB6B_41") (pintype "bidirectional"))
    )
    (net (code "97") (name "unconnected-(U1C-PB9A-Pad42)") (class "Default")
      (node (ref "U1") (pin "42") (pinfunction "PB9A_42") (pintype "bidirectional"))
    )
    (net (code "98") (name "unconnected-(U1C-PB9B-Pad43)") (class "Default")
      (node (ref "U1") (pin "43") (pinfunction "PB9B_43") (pintype "bidirectional"))
    )
    (net (code "99") (name "unconnected-(U1C-PB12A,_MCLK{slash}CCLK-Pad44)") (class "Default")
      (node (ref "U1") (pin "44") (pinfunction "PB12A,_MCLK/CCLK_44") (pintype "bidirectional"))
    )
    (net (code "100") (name "unconnected-(U1C-PB12B,_SO{slash}SPISO-Pad45)") (class "Default")
      (node (ref "U1") (pin "45") (pinfunction "PB12B,_SO/SPISO_45") (pintype "bidirectional"))
    )
    (net (code "101") (name "unconnected-(U1C-PB13A-Pad47)") (class "Default")
      (node (ref "U1") (pin "47") (pinfunction "PB13A_47") (pintype "bidirectional"))
    )
    (net (code "102") (name "unconnected-(U1C-PB13B-Pad48)") (class "Default")
      (node (ref "U1") (pin "48") (pinfunction "PB13B_48") (pintype "bidirectional"))
    )
    (net (code "103") (name "unconnected-(U1C-PB16A,_PCLKT2_0-Pad49)") (class "Default")
      (node (ref "U1") (pin "49") (pinfunction "PB16A,_PCLKT2_0_49") (pintype "bidirectional"))
    )
    (net (code "104") (name "unconnected-(U1C-PB16B,_PCLKC2_0-Pad50)") (class "Default")
      (node (ref "U1") (pin "50") (pinfunction "PB16B,_PCLKC2_0_50") (pintype "bidirectional"))
    )
    (net (code "105") (name "unconnected-(U1C-PB18A-Pad52)") (class "Default")
      (node (ref "U1") (pin "52") (pinfunction "PB18A_52") (pintype "bidirectional"))
    )
    (net (code "106") (name "unconnected-(U1C-PB18B-Pad54)") (class "Default")
      (node (ref "U1") (pin "54") (pinfunction "PB18B_54") (pintype "bidirectional"))
    )
    (net (code "107") (name "unconnected-(U1C-PB23A,_PCLKT2_1-Pad55)") (class "Default")
      (node (ref "U1") (pin "55") (pinfunction "PB23A,_PCLKT2_1_55") (pintype "bidirectional"))
    )
    (net (code "108") (name "unconnected-(U1C-PB23B,_PCLKC2_1-Pad56)") (class "Default")
      (node (ref "U1") (pin "56") (pinfunction "PB23B,_PCLKC2_1_56") (pintype "bidirectional"))
    )
    (net (code "109") (name "unconnected-(U1C-PB26A-Pad57)") (class "Default")
      (node (ref "U1") (pin "57") (pinfunction "PB26A_57") (pintype "bidirectional"))
    )
    (net (code "110") (name "unconnected-(U1C-PB26B-Pad58)") (class "Default")
      (node (ref "U1") (pin "58") (pinfunction "PB26B_58") (pintype "bidirectional"))
    )
    (net (code "111") (name "unconnected-(U1C-PB29A-Pad59)") (class "Default")
      (node (ref "U1") (pin "59") (pinfunction "PB29A_59") (pintype "bidirectional"))
    )
    (net (code "112") (name "unconnected-(U1C-PB29B-Pad60)") (class "Default")
      (node (ref "U1") (pin "60") (pinfunction "PB29B_60") (pintype "bidirectional"))
    )
    (net (code "113") (name "unconnected-(U1C-PB31A-Pad61)") (class "Default")
      (node (ref "U1") (pin "61") (pinfunction "PB31A_61") (pintype "bidirectional"))
    )
    (net (code "114") (name "unconnected-(U1C-PB31B-Pad62)") (class "Default")
      (node (ref "U1") (pin "62") (pinfunction "PB31B_62") (pintype "bidirectional"))
    )
    (net (code "115") (name "unconnected-(U1C-PB31D-Pad63)") (class "Default")
      (node (ref "U1") (pin "63") (pinfunction "PB31D_63") (pintype "bidirectional"))
    )
    (net (code "116") (name "unconnected-(U1C-PB35A-Pad65)") (class "Default")
      (node (ref "U1") (pin "65") (pinfunction "PB35A_65") (pintype "bidirectional"))
    )
    (net (code "117") (name "unconnected-(U1C-PB35B-Pad67)") (class "Default")
      (node (ref "U1") (pin "67") (pinfunction "PB35B_67") (pintype "bidirectional"))
    )
    (net (code "118") (name "unconnected-(U1C-PB37A-Pad68)") (class "Default")
      (node (ref "U1") (pin "68") (pinfunction "PB37A_68") (pintype "bidirectional"))
    )
    (net (code "119") (name "unconnected-(U1C-PB37B-Pad69)") (class "Default")
      (node (ref "U1") (pin "69") (pinfunction "PB37B_69") (pintype "bidirectional"))
    )
    (net (code "120") (name "unconnected-(U1C-PB38A,_SN-Pad70)") (class "Default")
      (node (ref "U1") (pin "70") (pinfunction "PB38A,_SN_70") (pintype "bidirectional"))
    )
    (net (code "121") (name "unconnected-(U1C-PB38B,_SI{slash}SISPI-Pad71)") (class "Default")
      (node (ref "U1") (pin "71") (pinfunction "PB38B,_SI/SISPI_71") (pintype "bidirectional"))
    )
    (net (code "122") (name "unconnected-(U1D-PL19A-Pad25)") (class "Default")
      (node (ref "U1") (pin "25") (pinfunction "PL19A_25") (pintype "bidirectional+no_connect"))
    )
    (net (code "123") (name "unconnected-(U1E-PL10A-Pad13)") (class "Default")
      (node (ref "U1") (pin "13") (pinfunction "PL10A_13") (pintype "bidirectional"))
    )
    (net (code "124") (name "unconnected-(U1E-PL10B-Pad14)") (class "Default")
      (node (ref "U1") (pin "14") (pinfunction "PL10B_14") (pintype "bidirectional"))
    )
    (net (code "125") (name "unconnected-(U1E-PL11A-Pad15)") (class "Default")
      (node (ref "U1") (pin "15") (pinfunction "PL11A_15") (pintype "bidirectional"))
    )
    (net (code "126") (name "unconnected-(U1E-PL11B-Pad17)") (class "Default")
      (node (ref "U1") (pin "17") (pinfunction "PL11B_17") (pintype "bidirectional"))
    )
    (net (code "127") (name "unconnected-(U1E-PL12A,_PCLKT4_0-Pad19)") (class "Default")
      (node (ref "U1") (pin "19") (pinfunction "PL12A,_PCLKT4_0_19") (pintype "bidirectional"))
    )
    (net (code "128") (name "unconnected-(U1E-PL12B,_PCLKC4_0-Pad20)") (class "Default")
      (node (ref "U1") (pin "20") (pinfunction "PL12B,_PCLKC4_0_20") (pintype "bidirectional"))
    )
    (net (code "129") (name "unconnected-(U1E-PL15A-Pad21)") (class "Default")
      (node (ref "U1") (pin "21") (pinfunction "PL15A_21") (pintype "bidirectional"))
    )
    (net (code "130") (name "unconnected-(U1E-PL15B-Pad22)") (class "Default")
      (node (ref "U1") (pin "22") (pinfunction "PL15B_22") (pintype "bidirectional"))
    )
    (net (code "131") (name "unconnected-(U1E-PL17A-Pad23)") (class "Default")
      (node (ref "U1") (pin "23") (pinfunction "PL17A_23") (pintype "bidirectional"))
    )
    (net (code "132") (name "unconnected-(U1E-PL17B-Pad24)") (class "Default")
      (node (ref "U1") (pin "24") (pinfunction "PL17B_24") (pintype "bidirectional"))
    )
  )
)
